# Board1.net
KiCad netlist of a schematic drawn in EasyEDA Pro
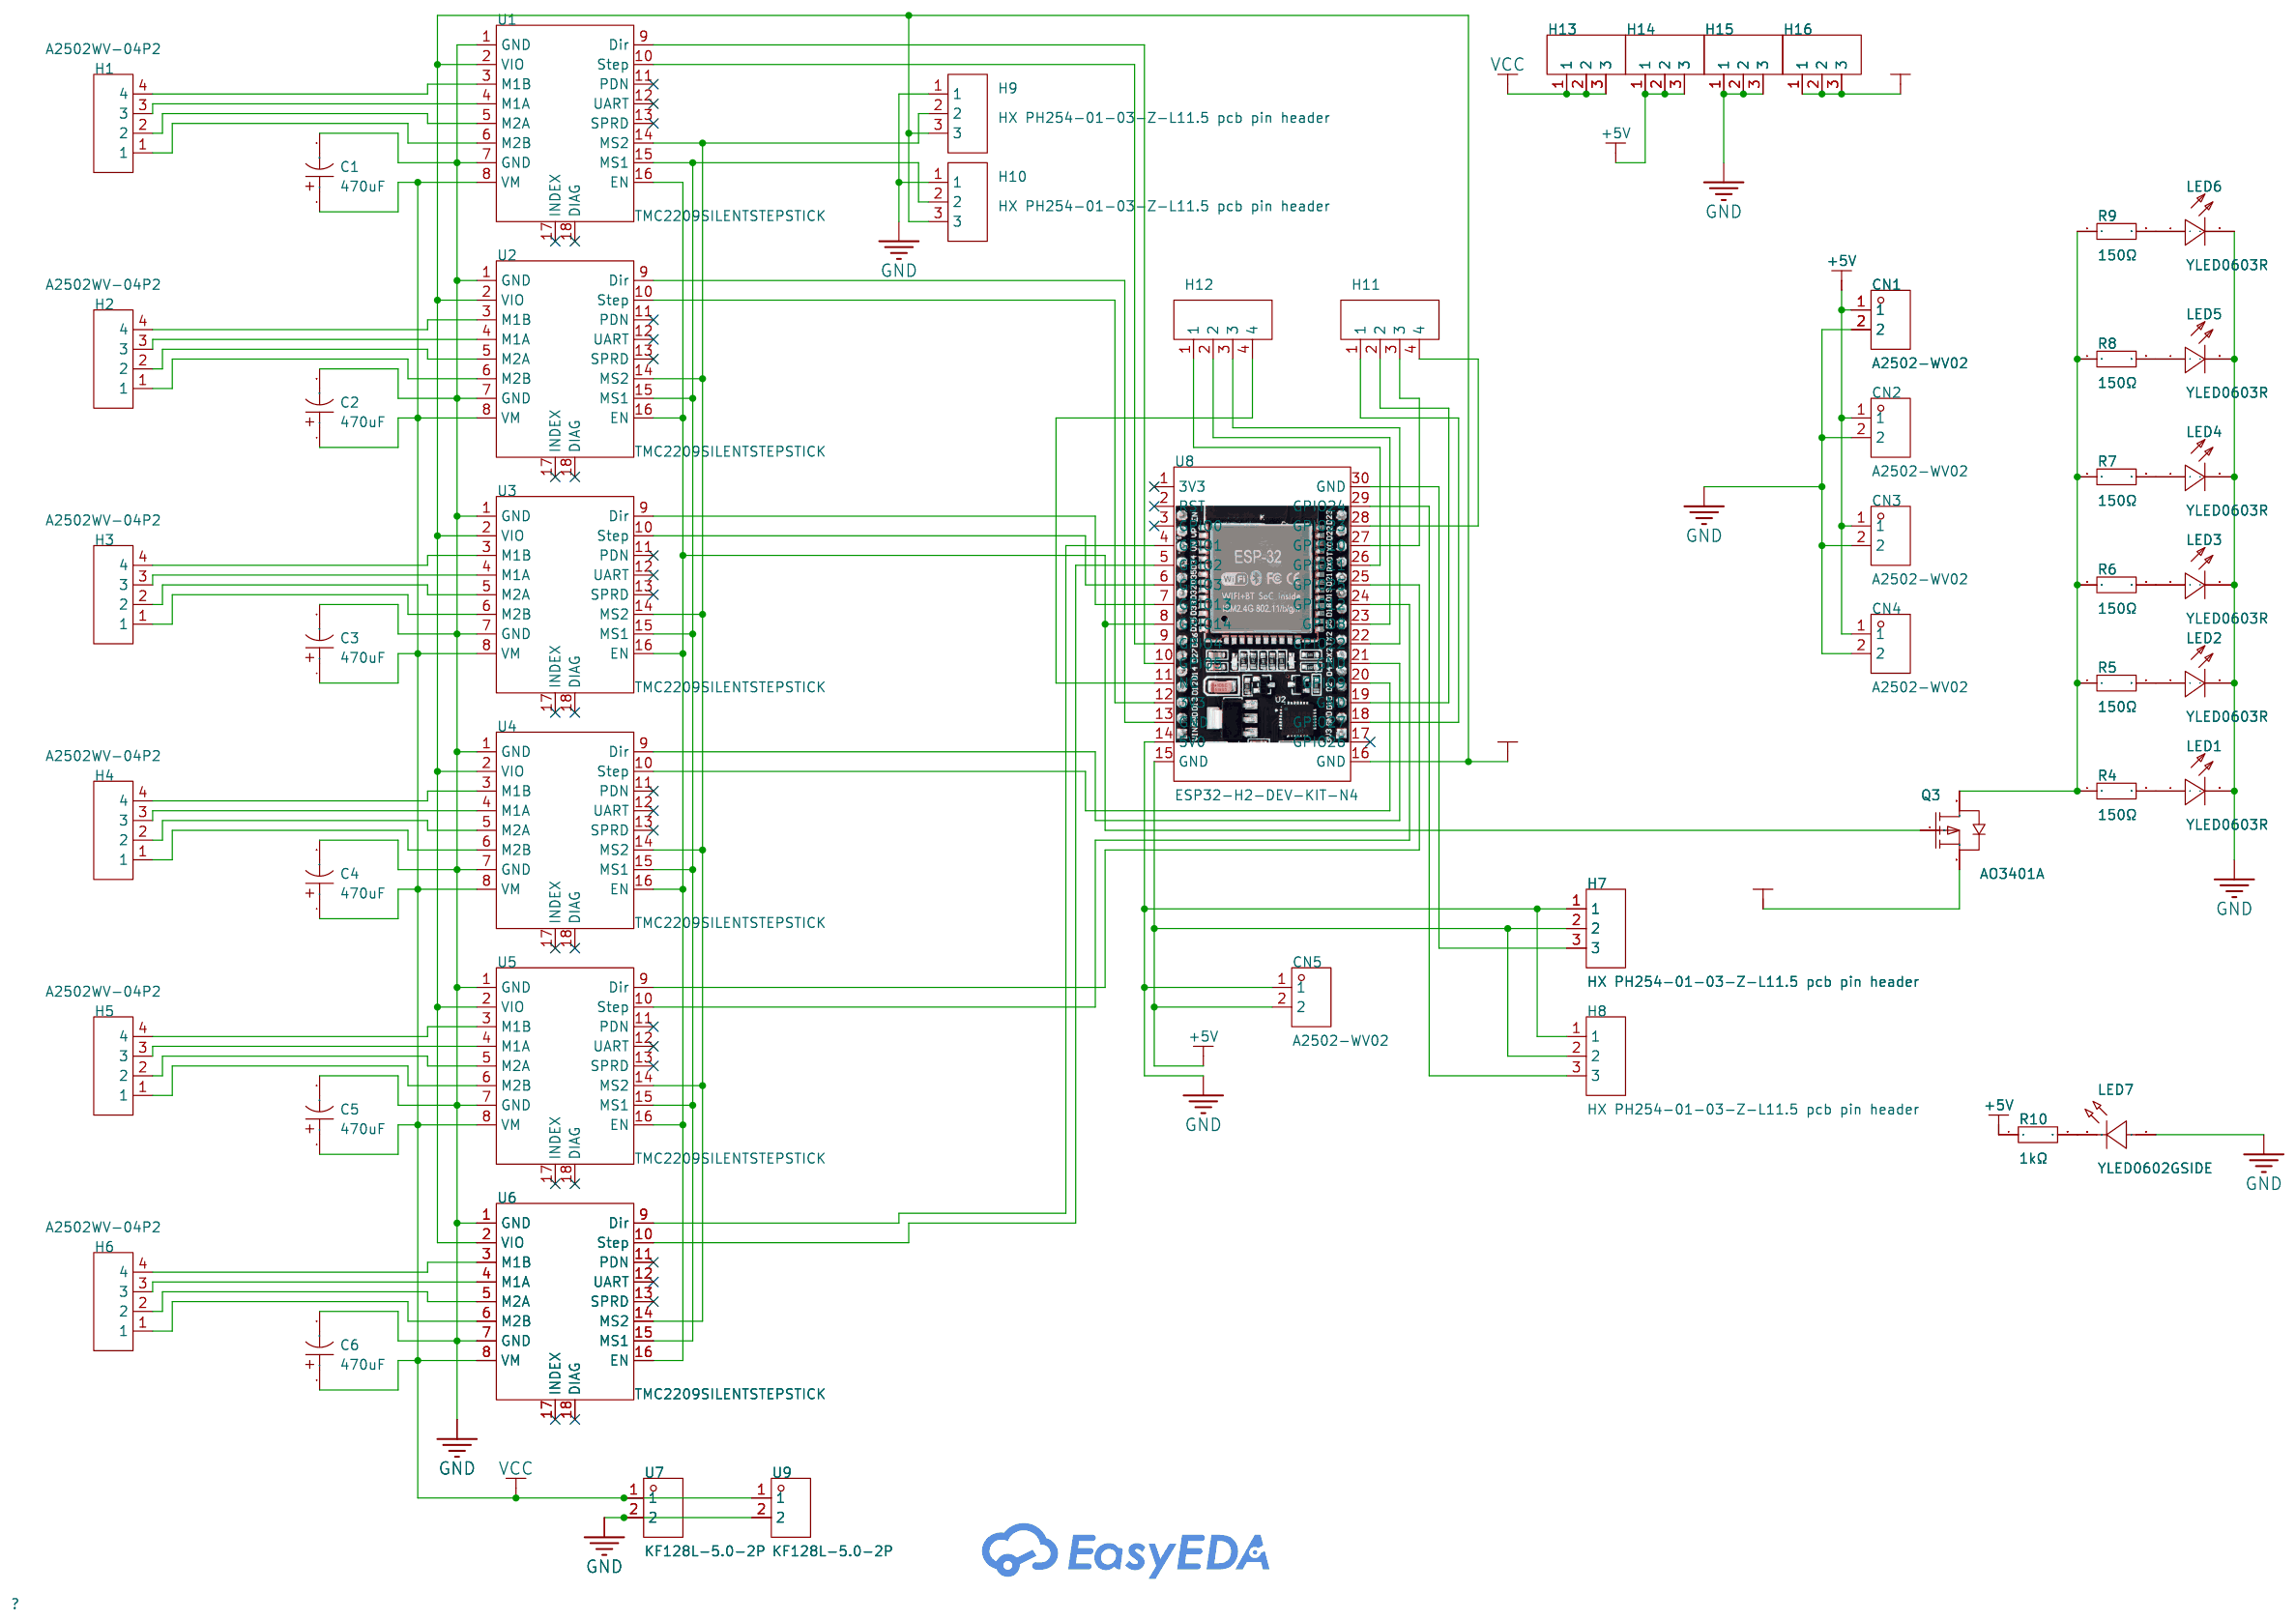
[diagram p0: schematic sheet]

(export (version "E")
  (design (tool "Eeschema 10.0.6"))
  (components
    (comp (ref "C1")
      (value "470uF")
      (footprint "easyedapro:CAP-TH_BD10.0-P5.00-D0.6-FD")
      (fields (field (name "Manufacturer Part") "50V470uF CD288") (field (name "Manufacturer") "HRK(鸿瑞凯电子)"))
      (libsource (lib "easyedapro") (part "50V470UF CD288"))
    )
    (comp (ref "C2")
      (value "470uF")
      (footprint "easyedapro:CAP-TH_BD10.0-P5.00-D0.6-FD")
      (fields (field (name "Manufacturer Part") "50V470uF CD288") (field (name "Manufacturer") "HRK(鸿瑞凯电子)"))
      (libsource (lib "easyedapro") (part "50V470UF CD288"))
    )
    (comp (ref "C3")
      (value "470uF")
      (footprint "easyedapro:CAP-TH_BD10.0-P5.00-D0.6-FD")
      (fields (field (name "Manufacturer Part") "50V470uF CD288") (field (name "Manufacturer") "HRK(鸿瑞凯电子)"))
      (libsource (lib "easyedapro") (part "50V470UF CD288"))
    )
    (comp (ref "C4")
      (value "470uF")
      (footprint "easyedapro:CAP-TH_BD10.0-P5.00-D0.6-FD")
      (fields (field (name "Manufacturer Part") "50V470uF CD288") (field (name "Manufacturer") "HRK(鸿瑞凯电子)"))
      (libsource (lib "easyedapro") (part "50V470UF CD288"))
    )
    (comp (ref "C5")
      (value "470uF")
      (footprint "easyedapro:CAP-TH_BD10.0-P5.00-D0.6-FD")
      (fields (field (name "Manufacturer Part") "50V470uF CD288") (field (name "Manufacturer") "HRK(鸿瑞凯电子)"))
      (libsource (lib "easyedapro") (part "50V470UF CD288"))
    )
    (comp (ref "C6")
      (value "470uF")
      (footprint "easyedapro:CAP-TH_BD10.0-P5.00-D0.6-FD")
      (fields (field (name "Manufacturer Part") "50V470uF CD288") (field (name "Manufacturer") "HRK(鸿瑞凯电子)"))
      (libsource (lib "easyedapro") (part "50V470UF CD288"))
    )
    (comp (ref "CN1")
      (value "A2502-WV02")
      (footprint "easyedapro:CONN-TH_A2502-WV02")
      (libsource (lib "easyedapro") (part "A2502-WV02"))
    )
    (comp (ref "CN2")
      (value "A2502-WV02")
      (footprint "easyedapro:CONN-TH_A2502-WV02")
      (libsource (lib "easyedapro") (part "A2502-WV02"))
    )
    (comp (ref "CN3")
      (value "A2502-WV02")
      (footprint "easyedapro:CONN-TH_A2502-WV02")
      (libsource (lib "easyedapro") (part "A2502-WV02"))
    )
    (comp (ref "CN4")
      (value "A2502-WV02")
      (footprint "easyedapro:CONN-TH_A2502-WV02")
      (libsource (lib "easyedapro") (part "A2502-WV02"))
    )
    (comp (ref "CN5")
      (value "A2502-WV02")
      (footprint "easyedapro:CONN-TH_A2502-WV02")
      (libsource (lib "easyedapro") (part "A2502-WV02"))
    )
    (comp (ref "H1")
      (value "A2502WV-04P2")
      (footprint "easyedapro:HDR-TH_4P-HX-PH254-01-04-Z-L11.5")
      (fields (field (name "Manufacturer") "HR(灿达)"))
      (libsource (lib "easyedapro") (part "HX PH254-01-04-Z-L11.5 STRAIGHT PIN HEADER"))
    )
    (comp (ref "H2")
      (value "A2502WV-04P2")
      (footprint "easyedapro:HDR-TH_4P-HX-PH254-01-04-Z-L11.5")
      (fields (field (name "Manufacturer") "HR(灿达)"))
      (libsource (lib "easyedapro") (part "HX PH254-01-04-Z-L11.5 STRAIGHT PIN HEADER"))
    )
    (comp (ref "H3")
      (value "A2502WV-04P2")
      (footprint "easyedapro:HDR-TH_4P-HX-PH254-01-04-Z-L11.5")
      (fields (field (name "Manufacturer") "HR(灿达)"))
      (libsource (lib "easyedapro") (part "HX PH254-01-04-Z-L11.5 STRAIGHT PIN HEADER"))
    )
    (comp (ref "H4")
      (value "A2502WV-04P2")
      (footprint "easyedapro:HDR-TH_4P-HX-PH254-01-04-Z-L11.5")
      (fields (field (name "Manufacturer") "HR(灿达)"))
      (libsource (lib "easyedapro") (part "HX PH254-01-04-Z-L11.5 STRAIGHT PIN HEADER"))
    )
    (comp (ref "H5")
      (value "A2502WV-04P2")
      (footprint "easyedapro:HDR-TH_4P-HX-PH254-01-04-Z-L11.5")
      (fields (field (name "Manufacturer") "HR(灿达)"))
      (libsource (lib "easyedapro") (part "HX PH254-01-04-Z-L11.5 STRAIGHT PIN HEADER"))
    )
    (comp (ref "H6")
      (value "A2502WV-04P2")
      (footprint "easyedapro:HDR-TH_4P-HX-PH254-01-04-Z-L11.5")
      (fields (field (name "Manufacturer") "HR(灿达)"))
      (libsource (lib "easyedapro") (part "HX PH254-01-04-Z-L11.5 STRAIGHT PIN HEADER"))
    )
    (comp (ref "H7")
      (value "HX PH254-01-03-Z-L11.5 pcb pin header")
      (footprint "easyedapro:HDR-TH_3P-P2.54-V-M-1")
      (fields (field (name "Manufacturer") "hanxia(韩下)"))
      (libsource (lib "easyedapro") (part "HX PH254-01-03-Z-L11.5 PCB PIN HEADER"))
    )
    (comp (ref "H8")
      (value "HX PH254-01-03-Z-L11.5 pcb pin header")
      (footprint "easyedapro:HDR-TH_3P-P2.54-V-M-1")
      (fields (field (name "Manufacturer") "hanxia(韩下)"))
      (libsource (lib "easyedapro") (part "HX PH254-01-03-Z-L11.5 PCB PIN HEADER"))
    )
    (comp (ref "H9")
      (value "HX PH254-01-03-Z-L11.5 pcb pin header")
      (footprint "easyedapro:HDR-TH_3P-P2.54-V-M-1")
      (fields (field (name "Manufacturer") "hanxia(韩下)"))
      (libsource (lib "easyedapro") (part "HX PH254-01-03-Z-L11.5 PCB PIN HEADER"))
    )
    (comp (ref "H10")
      (value "HX PH254-01-03-Z-L11.5 pcb pin header")
      (footprint "easyedapro:HDR-TH_3P-P2.54-V-M-1")
      (fields (field (name "Manufacturer") "hanxia(韩下)"))
      (libsource (lib "easyedapro") (part "HX PH254-01-03-Z-L11.5 PCB PIN HEADER"))
    )
    (comp (ref "H11")
      (value "HX PH254-01-04-Z-L11.5 straight pin header")
      (footprint "easyedapro:HDR-TH_4P-HX-PH254-01-04-Z-L11.5")
      (fields (field (name "Manufacturer") "hanxia(韩下)"))
      (libsource (lib "easyedapro") (part "HX PH254-01-04-Z-L11.5 STRAIGHT PIN HEADER"))
    )
    (comp (ref "H12")
      (value "HX PH254-01-04-Z-L11.5 straight pin header")
      (footprint "easyedapro:HDR-TH_4P-HX-PH254-01-04-Z-L11.5")
      (fields (field (name "Manufacturer") "hanxia(韩下)"))
      (libsource (lib "easyedapro") (part "HX PH254-01-04-Z-L11.5 STRAIGHT PIN HEADER"))
    )
    (comp (ref "H13")
      (value "HX PH254-01-03-Z-L11.5 pcb pin header")
      (footprint "easyedapro:HDR-TH_3P-P2.54-V-M-1")
      (fields (field (name "Manufacturer") "hanxia(韩下)"))
      (libsource (lib "easyedapro") (part "HX PH254-01-03-Z-L11.5 PCB PIN HEADER"))
    )
    (comp (ref "H14")
      (value "HX PH254-01-03-Z-L11.5 pcb pin header")
      (footprint "easyedapro:HDR-TH_3P-P2.54-V-M-1")
      (fields (field (name "Manufacturer") "hanxia(韩下)"))
      (libsource (lib "easyedapro") (part "HX PH254-01-03-Z-L11.5 PCB PIN HEADER"))
    )
    (comp (ref "H15")
      (value "HX PH254-01-03-Z-L11.5 pcb pin header")
      (footprint "easyedapro:HDR-TH_3P-P2.54-V-M-1")
      (fields (field (name "Manufacturer") "hanxia(韩下)"))
      (libsource (lib "easyedapro") (part "HX PH254-01-03-Z-L11.5 PCB PIN HEADER"))
    )
    (comp (ref "H16")
      (value "HX PH254-01-03-Z-L11.5 pcb pin header")
      (footprint "easyedapro:HDR-TH_3P-P2.54-V-M-1")
      (fields (field (name "Manufacturer") "hanxia(韩下)"))
      (libsource (lib "easyedapro") (part "HX PH254-01-03-Z-L11.5 PCB PIN HEADER"))
    )
    (comp (ref "LED1")
      (value "YLED0603R")
      (footprint "easyedapro:LED0603-FD")
      (fields (field (name "Manufacturer") "YONGYUTAI(永裕泰)"))
      (libsource (lib "easyedapro") (part "YLED0603R"))
    )
    (comp (ref "LED2")
      (value "YLED0603R")
      (footprint "easyedapro:LED0603-FD")
      (fields (field (name "Manufacturer") "YONGYUTAI(永裕泰)"))
      (libsource (lib "easyedapro") (part "YLED0603R"))
    )
    (comp (ref "LED3")
      (value "YLED0603R")
      (footprint "easyedapro:LED0603-FD")
      (fields (field (name "Manufacturer") "YONGYUTAI(永裕泰)"))
      (libsource (lib "easyedapro") (part "YLED0603R"))
    )
    (comp (ref "LED4")
      (value "YLED0603R")
      (footprint "easyedapro:LED0603-FD")
      (fields (field (name "Manufacturer") "YONGYUTAI(永裕泰)"))
      (libsource (lib "easyedapro") (part "YLED0603R"))
    )
    (comp (ref "LED5")
      (value "YLED0603R")
      (footprint "easyedapro:LED0603-FD")
      (fields (field (name "Manufacturer") "YONGYUTAI(永裕泰)"))
      (libsource (lib "easyedapro") (part "YLED0603R"))
    )
    (comp (ref "LED6")
      (value "YLED0603R")
      (footprint "easyedapro:LED0603-FD")
      (fields (field (name "Manufacturer") "YONGYUTAI(永裕泰)"))
      (libsource (lib "easyedapro") (part "YLED0603R"))
    )
    (comp (ref "LED7")
      (value "YLED0602GSIDE")
      (footprint "easyedapro:LED-SMD_L1.6-W1.1-R-RD_GREEN")
      (fields (field (name "Manufacturer") "YONGYUTAI(永裕泰)"))
      (libsource (lib "easyedapro") (part "YLED0602GSIDE"))
    )
    (comp (ref "Q3")
      (value "AO3401A")
      (footprint "easyedapro:SOT-23-3_L2.9-W1.3-P1.90-LS2.4-BR")
      (fields (field (name "Manufacturer") "FUXINSEMI(富芯森美)"))
      (libsource (lib "easyedapro") (part "AO3401A_C5380686"))
    )
    (comp (ref "R4")
      (value "150Ω")
      (footprint "easyedapro:R0603")
      (fields (field (name "Manufacturer Part") "RMC06031505%N") (field (name "Manufacturer") "Tyohm(幸亚电阻)"))
      (libsource (lib "easyedapro") (part "0603WAF1001T5E"))
    )
    (comp (ref "R5")
      (value "150Ω")
      (footprint "easyedapro:R0603")
      (fields (field (name "Manufacturer Part") "RMC06031505%N") (field (name "Manufacturer") "Tyohm(幸亚电阻)"))
      (libsource (lib "easyedapro") (part "0603WAF1001T5E"))
    )
    (comp (ref "R6")
      (value "150Ω")
      (footprint "easyedapro:R0603")
      (fields (field (name "Manufacturer Part") "RMC06031505%N") (field (name "Manufacturer") "Tyohm(幸亚电阻)"))
      (libsource (lib "easyedapro") (part "0603WAF1001T5E"))
    )
    (comp (ref "R7")
      (value "150Ω")
      (footprint "easyedapro:R0603")
      (fields (field (name "Manufacturer Part") "RMC06031505%N") (field (name "Manufacturer") "Tyohm(幸亚电阻)"))
      (libsource (lib "easyedapro") (part "0603WAF1001T5E"))
    )
    (comp (ref "R8")
      (value "150Ω")
      (footprint "easyedapro:R0603")
      (fields (field (name "Manufacturer Part") "RMC06031505%N") (field (name "Manufacturer") "Tyohm(幸亚电阻)"))
      (libsource (lib "easyedapro") (part "0603WAF1001T5E"))
    )
    (comp (ref "R9")
      (value "150Ω")
      (footprint "easyedapro:R0603")
      (fields (field (name "Manufacturer Part") "RMC06031505%N") (field (name "Manufacturer") "Tyohm(幸亚电阻)"))
      (libsource (lib "easyedapro") (part "0603WAF1001T5E"))
    )
    (comp (ref "R10")
      (value "1kΩ")
      (footprint "easyedapro:R0603")
      (fields
        (field (name "Manufacturer Part") "0603WAF1001T5E")
        (field (name "Manufacturer") "UNI-ROYAL(厚声)")
      )
      (libsource (lib "easyedapro") (part "0603WAF1001T5E"))
    )
    (comp (ref "U1")
      (value "TMC2209SILENTSTEPSTICK")
      (footprint "easyedapro:COMM-TH_TMC2209SILENTSTEPSTICK")
      (description "Type:Power Management")
      (fields (field (name "Manufacturer") "TRINAMIC"))
      (libsource (lib "easyedapro") (part "TMC2209SILENTSTEPSTICK"))
    )
    (comp (ref "U2")
      (value "TMC2209SILENTSTEPSTICK")
      (footprint "easyedapro:COMM-TH_TMC2209SILENTSTEPSTICK")
      (description "Type:Power Management")
      (fields (field (name "Manufacturer") "TRINAMIC"))
      (libsource (lib "easyedapro") (part "TMC2209SILENTSTEPSTICK"))
    )
    (comp (ref "U3")
      (value "TMC2209SILENTSTEPSTICK")
      (footprint "easyedapro:COMM-TH_TMC2209SILENTSTEPSTICK")
      (description "Type:Power Management")
      (fields (field (name "Manufacturer") "TRINAMIC"))
      (libsource (lib "easyedapro") (part "TMC2209SILENTSTEPSTICK"))
    )
    (comp (ref "U4")
      (value "TMC2209SILENTSTEPSTICK")
      (footprint "easyedapro:COMM-TH_TMC2209SILENTSTEPSTICK")
      (description "Type:Power Management")
      (fields (field (name "Manufacturer") "TRINAMIC"))
      (libsource (lib "easyedapro") (part "TMC2209SILENTSTEPSTICK"))
    )
    (comp (ref "U5")
      (value "TMC2209SILENTSTEPSTICK")
      (footprint "easyedapro:COMM-TH_TMC2209SILENTSTEPSTICK")
      (description "Type:Power Management")
      (fields (field (name "Manufacturer") "TRINAMIC"))
      (libsource (lib "easyedapro") (part "TMC2209SILENTSTEPSTICK"))
    )
    (comp (ref "U6")
      (value "TMC2209SILENTSTEPSTICK")
      (footprint "easyedapro:COMM-TH_TMC2209SILENTSTEPSTICK")
      (description "Type:Power Management")
      (fields (field (name "Manufacturer") "TRINAMIC"))
      (libsource (lib "easyedapro") (part "TMC2209SILENTSTEPSTICK"))
    )
    (comp (ref "U7")
      (value "KF128L-5.0-2P")
      (footprint "easyedapro:CONN-TH_P5.00_KF128L-5.0-2P")
      (fields (field (name "Manufacturer") "KEFA(科发)"))
      (libsource (lib "easyedapro") (part "KF128L-5.0-2P"))
    )
    (comp (ref "U8")
      (value "ESP32-H2-DEV-KIT-N4")
      (footprint "easyedapro:COMM-TH_L51.6-W25.4-P2.54-LS22.86")
      (libsource (lib "easyedapro") (part "ESP32-H2-DEV-KIT-N4"))
    )
    (comp (ref "U9")
      (value "KF128L-5.0-2P")
      (footprint "easyedapro:CONN-TH_P5.00_KF128L-5.0-2P")
      (fields (field (name "Manufacturer") "KEFA(科发)"))
      (libsource (lib "easyedapro") (part "KF128L-5.0-2P"))
    )
  )
  (nets
    (net (code "1") (name "+3V3") (class "Default")
      (node (ref "H10") (pin "3") (pinfunction "3_3") (pintype "unspecified"))
      (node (ref "H16") (pin "1") (pinfunction "1_1") (pintype "unspecified"))
      (node (ref "H16") (pin "2") (pinfunction "2_2") (pintype "unspecified"))
      (node (ref "H16") (pin "3") (pinfunction "3_3") (pintype "unspecified"))
      (node (ref "H9") (pin "3") (pinfunction "3_3") (pintype "unspecified"))
      (node (ref "Q3") (pin "2") (pinfunction "S_2") (pintype "unspecified"))
      (node (ref "U1") (pin "2") (pinfunction "VIO_2") (pintype "unspecified"))
      (node (ref "U2") (pin "2") (pinfunction "VIO_2") (pintype "unspecified"))
      (node (ref "U3") (pin "2") (pinfunction "VIO_2") (pintype "unspecified"))
      (node (ref "U4") (pin "2") (pinfunction "VIO_2") (pintype "unspecified"))
      (node (ref "U5") (pin "2") (pinfunction "VIO_2") (pintype "unspecified"))
      (node (ref "U6") (pin "2") (pinfunction "VIO_2") (pintype "unspecified"))
      (node (ref "U8") (pin "16") (pinfunction "GND_16") (pintype "unspecified"))
    )
    (net (code "2") (name "+5V") (class "Default")
      (node (ref "CN1") (pin "1") (pinfunction "1_1") (pintype "unspecified"))
      (node (ref "CN2") (pin "1") (pinfunction "1_1") (pintype "unspecified"))
      (node (ref "CN3") (pin "1") (pinfunction "1_1") (pintype "unspecified"))
      (node (ref "CN4") (pin "1") (pinfunction "1_1") (pintype "unspecified"))
      (node (ref "CN5") (pin "2") (pinfunction "2_2") (pintype "unspecified"))
      (node (ref "H14") (pin "1") (pinfunction "1_1") (pintype "unspecified"))
      (node (ref "H14") (pin "2") (pinfunction "2_2") (pintype "unspecified"))
      (node (ref "H14") (pin "3") (pinfunction "3_3") (pintype "unspecified"))
      (node (ref "H7") (pin "2") (pinfunction "2_2") (pintype "unspecified"))
      (node (ref "H8") (pin "2") (pinfunction "2_2") (pintype "unspecified"))
      (node (ref "R10") (pin "1") (pinfunction "1_1") (pintype "input"))
      (node (ref "U8") (pin "15") (pinfunction "GND_15") (pintype "unspecified"))
    )
    (net (code "3") (name "GND") (class "Default")
      (node (ref "C1") (pin "2") (pinfunction "2_2") (pintype "input"))
      (node (ref "C2") (pin "2") (pinfunction "2_2") (pintype "input"))
      (node (ref "C3") (pin "2") (pinfunction "2_2") (pintype "input"))
      (node (ref "C4") (pin "2") (pinfunction "2_2") (pintype "input"))
      (node (ref "C5") (pin "2") (pinfunction "2_2") (pintype "input"))
      (node (ref "C6") (pin "2") (pinfunction "2_2") (pintype "input"))
      (node (ref "CN1") (pin "2") (pinfunction "2_2") (pintype "unspecified"))
      (node (ref "CN2") (pin "2") (pinfunction "2_2") (pintype "unspecified"))
      (node (ref "CN3") (pin "2") (pinfunction "2_2") (pintype "unspecified"))
      (node (ref "CN4") (pin "2") (pinfunction "2_2") (pintype "unspecified"))
      (node (ref "CN5") (pin "1") (pinfunction "1_1") (pintype "unspecified"))
      (node (ref "H10") (pin "1") (pinfunction "1_1") (pintype "unspecified"))
      (node (ref "H15") (pin "1") (pinfunction "1_1") (pintype "unspecified"))
      (node (ref "H15") (pin "2") (pinfunction "2_2") (pintype "unspecified"))
      (node (ref "H15") (pin "3") (pinfunction "3_3") (pintype "unspecified"))
      (node (ref "H7") (pin "1") (pinfunction "1_1") (pintype "unspecified"))
      (node (ref "H8") (pin "1") (pinfunction "1_1") (pintype "unspecified"))
      (node (ref "H9") (pin "1") (pinfunction "1_1") (pintype "unspecified"))
      (node (ref "LED1") (pin "2") (pinfunction "-_2") (pintype "unspecified"))
      (node (ref "LED2") (pin "2") (pinfunction "-_2") (pintype "unspecified"))
      (node (ref "LED3") (pin "2") (pinfunction "-_2") (pintype "unspecified"))
      (node (ref "LED4") (pin "2") (pinfunction "-_2") (pintype "unspecified"))
      (node (ref "LED5") (pin "2") (pinfunction "-_2") (pintype "unspecified"))
      (node (ref "LED6") (pin "2") (pinfunction "-_2") (pintype "unspecified"))
      (node (ref "LED7") (pin "1") (pinfunction "A_1") (pintype "unspecified"))
      (node (ref "U1") (pin "1") (pinfunction "GND_1") (pintype "unspecified"))
      (node (ref "U1") (pin "7") (pinfunction "GND_7") (pintype "unspecified"))
      (node (ref "U2") (pin "1") (pinfunction "GND_1") (pintype "unspecified"))
      (node (ref "U2") (pin "7") (pinfunction "GND_7") (pintype "unspecified"))
      (node (ref "U3") (pin "1") (pinfunction "GND_1") (pintype "unspecified"))
      (node (ref "U3") (pin "7") (pinfunction "GND_7") (pintype "unspecified"))
      (node (ref "U4") (pin "1") (pinfunction "GND_1") (pintype "unspecified"))
      (node (ref "U4") (pin "7") (pinfunction "GND_7") (pintype "unspecified"))
      (node (ref "U5") (pin "1") (pinfunction "GND_1") (pintype "unspecified"))
      (node (ref "U5") (pin "7") (pinfunction "GND_7") (pintype "unspecified"))
      (node (ref "U6") (pin "1") (pinfunction "GND_1") (pintype "unspecified"))
      (node (ref "U6") (pin "7") (pinfunction "GND_7") (pintype "unspecified"))
      (node (ref "U7") (pin "2") (pinfunction "2_2") (pintype "unspecified"))
      (node (ref "U8") (pin "14") (pinfunction "5V0_14") (pintype "unspecified"))
      (node (ref "U9") (pin "2") (pinfunction "2_2") (pintype "unspecified"))
    )
    (net (code "4") (name "Net-(H7-Pad3)") (class "Default")
      (node (ref "H7") (pin "3") (pinfunction "3_3") (pintype "unspecified"))
      (node (ref "U8") (pin "30") (pinfunction "GND_30") (pintype "unspecified"))
    )
    (net (code "5") (name "Net-(H11-Pad2)") (class "Default")
      (node (ref "H11") (pin "2") (pinfunction "2_2") (pintype "unspecified"))
      (node (ref "U8") (pin "19") (pinfunction "GND_19") (pintype "unspecified"))
    )
    (net (code "6") (name "Net-(LED1-+)") (class "Default")
      (node (ref "LED1") (pin "1") (pinfunction "+_1") (pintype "unspecified"))
      (node (ref "R4") (pin "2") (pinfunction "2_2") (pintype "input"))
    )
    (net (code "7") (name "Net-(LED2-+)") (class "Default")
      (node (ref "LED2") (pin "1") (pinfunction "+_1") (pintype "unspecified"))
      (node (ref "R5") (pin "2") (pinfunction "2_2") (pintype "input"))
    )
    (net (code "8") (name "Net-(LED3-+)") (class "Default")
      (node (ref "LED3") (pin "1") (pinfunction "+_1") (pintype "unspecified"))
      (node (ref "R6") (pin "2") (pinfunction "2_2") (pintype "input"))
    )
    (net (code "9") (name "Net-(LED4-+)") (class "Default")
      (node (ref "LED4") (pin "1") (pinfunction "+_1") (pintype "unspecified"))
      (node (ref "R7") (pin "2") (pinfunction "2_2") (pintype "input"))
    )
    (net (code "10") (name "Net-(LED5-+)") (class "Default")
      (node (ref "LED5") (pin "1") (pinfunction "+_1") (pintype "unspecified"))
      (node (ref "R8") (pin "2") (pinfunction "2_2") (pintype "input"))
    )
    (net (code "11") (name "Net-(LED6-+)") (class "Default")
      (node (ref "LED6") (pin "1") (pinfunction "+_1") (pintype "unspecified"))
      (node (ref "R9") (pin "2") (pinfunction "2_2") (pintype "input"))
    )
    (net (code "12") (name "Net-(LED7-K)") (class "Default")
      (node (ref "LED7") (pin "2") (pinfunction "K_2") (pintype "unspecified"))
      (node (ref "R10") (pin "2") (pinfunction "2_2") (pintype "input"))
    )
    (net (code "13") (name "Net-(Q3-D)") (class "Default")
      (node (ref "Q3") (pin "3") (pinfunction "D_3") (pintype "unspecified"))
      (node (ref "R4") (pin "1") (pinfunction "1_1") (pintype "input"))
      (node (ref "R5") (pin "1") (pinfunction "1_1") (pintype "input"))
      (node (ref "R6") (pin "1") (pinfunction "1_1") (pintype "input"))
      (node (ref "R7") (pin "1") (pinfunction "1_1") (pintype "input"))
      (node (ref "R8") (pin "1") (pinfunction "1_1") (pintype "input"))
      (node (ref "R9") (pin "1") (pinfunction "1_1") (pintype "input"))
    )
    (net (code "14") (name "Net-(Q3-G)") (class "Default")
      (node (ref "Q3") (pin "1") (pinfunction "G_1") (pintype "unspecified"))
      (node (ref "U1") (pin "16") (pinfunction "EN_16") (pintype "unspecified"))
      (node (ref "U2") (pin "16") (pinfunction "EN_16") (pintype "unspecified"))
      (node (ref "U3") (pin "16") (pinfunction "EN_16") (pintype "unspecified"))
      (node (ref "U4") (pin "16") (pinfunction "EN_16") (pintype "unspecified"))
      (node (ref "U5") (pin "16") (pinfunction "EN_16") (pintype "unspecified"))
      (node (ref "U6") (pin "16") (pinfunction "EN_16") (pintype "unspecified"))
      (node (ref "U8") (pin "8") (pinfunction "GPIO14_8") (pintype "unspecified"))
    )
    (net (code "15") (name "Net-(U1-Dir)") (class "Default")
      (node (ref "U1") (pin "9") (pinfunction "Dir_9") (pintype "unspecified"))
      (node (ref "U8") (pin "10") (pinfunction "GPIO5_10") (pintype "unspecified"))
    )
    (net (code "16") (name "Net-(U1-M1A)") (class "Default")
      (node (ref "H1") (pin "3") (pinfunction "3_3") (pintype "unspecified"))
      (node (ref "U1") (pin "4") (pinfunction "M1A_4") (pintype "unspecified"))
    )
    (net (code "17") (name "Net-(U1-M1B)") (class "Default")
      (node (ref "H1") (pin "4") (pinfunction "4_4") (pintype "unspecified"))
      (node (ref "U1") (pin "3") (pinfunction "M1B_3") (pintype "unspecified"))
    )
    (net (code "18") (name "Net-(U1-M2A)") (class "Default")
      (node (ref "H1") (pin "2") (pinfunction "2_2") (pintype "unspecified"))
      (node (ref "U1") (pin "5") (pinfunction "M2A_5") (pintype "unspecified"))
    )
    (net (code "19") (name "Net-(U1-M2B)") (class "Default")
      (node (ref "H1") (pin "1") (pinfunction "1_1") (pintype "unspecified"))
      (node (ref "U1") (pin "6") (pinfunction "M2B_6") (pintype "unspecified"))
    )
    (net (code "20") (name "Net-(U1-MS1)") (class "Default")
      (node (ref "H10") (pin "2") (pinfunction "2_2") (pintype "unspecified"))
      (node (ref "U1") (pin "15") (pinfunction "MS1_15") (pintype "unspecified"))
      (node (ref "U2") (pin "15") (pinfunction "MS1_15") (pintype "unspecified"))
      (node (ref "U3") (pin "15") (pinfunction "MS1_15") (pintype "unspecified"))
      (node (ref "U4") (pin "15") (pinfunction "MS1_15") (pintype "unspecified"))
      (node (ref "U5") (pin "15") (pinfunction "MS1_15") (pintype "unspecified"))
      (node (ref "U6") (pin "15") (pinfunction "MS1_15") (pintype "unspecified"))
    )
    (net (code "21") (name "Net-(U1-MS2)") (class "Default")
      (node (ref "H9") (pin "2") (pinfunction "2_2") (pintype "unspecified"))
      (node (ref "U1") (pin "14") (pinfunction "MS2_14") (pintype "unspecified"))
      (node (ref "U2") (pin "14") (pinfunction "MS2_14") (pintype "unspecified"))
      (node (ref "U3") (pin "14") (pinfunction "MS2_14") (pintype "unspecified"))
      (node (ref "U4") (pin "14") (pinfunction "MS2_14") (pintype "unspecified"))
      (node (ref "U5") (pin "14") (pinfunction "MS2_14") (pintype "unspecified"))
      (node (ref "U6") (pin "14") (pinfunction "MS2_14") (pintype "unspecified"))
    )
    (net (code "22") (name "Net-(U1-Step)") (class "Default")
      (node (ref "U1") (pin "10") (pinfunction "Step_10") (pintype "unspecified"))
      (node (ref "U8") (pin "9") (pinfunction "GPIO4_9") (pintype "unspecified"))
    )
    (net (code "23") (name "Net-(U2-Dir)") (class "Default")
      (node (ref "U2") (pin "9") (pinfunction "Dir_9") (pintype "unspecified"))
      (node (ref "U8") (pin "13") (pinfunction "GND_13") (pintype "unspecified"))
    )
    (net (code "24") (name "Net-(U2-M1A)") (class "Default")
      (node (ref "H2") (pin "3") (pinfunction "3_3") (pintype "unspecified"))
      (node (ref "U2") (pin "4") (pinfunction "M1A_4") (pintype "unspecified"))
    )
    (net (code "25") (name "Net-(U2-M1B)") (class "Default")
      (node (ref "H2") (pin "4") (pinfunction "4_4") (pintype "unspecified"))
      (node (ref "U2") (pin "3") (pinfunction "M1B_3") (pintype "unspecified"))
    )
    (net (code "26") (name "Net-(U2-M2A)") (class "Default")
      (node (ref "H2") (pin "2") (pinfunction "2_2") (pintype "unspecified"))
      (node (ref "U2") (pin "5") (pinfunction "M2A_5") (pintype "unspecified"))
    )
    (net (code "27") (name "Net-(U2-M2B)") (class "Default")
      (node (ref "H2") (pin "1") (pinfunction "1_1") (pintype "unspecified"))
      (node (ref "U2") (pin "6") (pinfunction "M2B_6") (pintype "unspecified"))
    )
    (net (code "28") (name "Net-(U2-Step)") (class "Default")
      (node (ref "U2") (pin "10") (pinfunction "Step_10") (pintype "unspecified"))
      (node (ref "U8") (pin "12") (pinfunction "3V3_12") (pintype "unspecified"))
    )
    (net (code "29") (name "Net-(U3-Dir)") (class "Default")
      (node (ref "U3") (pin "9") (pinfunction "Dir_9") (pintype "unspecified"))
      (node (ref "U8") (pin "7") (pinfunction "GPIO13_7") (pintype "unspecified"))
    )
    (net (code "30") (name "Net-(U3-M1A)") (class "Default")
      (node (ref "H3") (pin "3") (pinfunction "3_3") (pintype "unspecified"))
      (node (ref "U3") (pin "4") (pinfunction "M1A_4") (pintype "unspecified"))
    )
    (net (code "31") (name "Net-(U3-M1B)") (class "Default")
      (node (ref "H3") (pin "4") (pinfunction "4_4") (pintype "unspecified"))
      (node (ref "U3") (pin "3") (pinfunction "M1B_3") (pintype "unspecified"))
    )
    (net (code "32") (name "Net-(U3-M2A)") (class "Default")
      (node (ref "H3") (pin "2") (pinfunction "2_2") (pintype "unspecified"))
      (node (ref "U3") (pin "5") (pinfunction "M2A_5") (pintype "unspecified"))
    )
    (net (code "33") (name "Net-(U3-M2B)") (class "Default")
      (node (ref "H3") (pin "1") (pinfunction "1_1") (pintype "unspecified"))
      (node (ref "U3") (pin "6") (pinfunction "M2B_6") (pintype "unspecified"))
    )
    (net (code "34") (name "Net-(U3-Step)") (class "Default")
      (node (ref "U3") (pin "10") (pinfunction "Step_10") (pintype "unspecified"))
      (node (ref "U8") (pin "6") (pinfunction "GPIO3_6") (pintype "unspecified"))
    )
    (net (code "35") (name "Net-(U4-Dir)") (class "Default")
      (node (ref "U4") (pin "9") (pinfunction "Dir_9") (pintype "unspecified"))
      (node (ref "U8") (pin "21") (pinfunction "GND_21") (pintype "unspecified"))
    )
    (net (code "36") (name "Net-(U4-M1A)") (class "Default")
      (node (ref "H4") (pin "3") (pinfunction "3_3") (pintype "unspecified"))
      (node (ref "U4") (pin "4") (pinfunction "M1A_4") (pintype "unspecified"))
    )
    (net (code "37") (name "Net-(U4-M1B)") (class "Default")
      (node (ref "H4") (pin "4") (pinfunction "4_4") (pintype "unspecified"))
      (node (ref "U4") (pin "3") (pinfunction "M1B_3") (pintype "unspecified"))
    )
    (net (code "38") (name "Net-(U4-M2A)") (class "Default")
      (node (ref "H4") (pin "2") (pinfunction "2_2") (pintype "unspecified"))
      (node (ref "U4") (pin "5") (pinfunction "M2A_5") (pintype "unspecified"))
    )
    (net (code "39") (name "Net-(U4-M2B)") (class "Default")
      (node (ref "H4") (pin "1") (pinfunction "1_1") (pintype "unspecified"))
      (node (ref "U4") (pin "6") (pinfunction "M2B_6") (pintype "unspecified"))
    )
    (net (code "40") (name "Net-(U4-Step)") (class "Default")
      (node (ref "U4") (pin "10") (pinfunction "Step_10") (pintype "unspecified"))
      (node (ref "U8") (pin "20") (pinfunction "GPIO9_20") (pintype "unspecified"))
    )
    (net (code "41") (name "Net-(U5-Dir)") (class "Default")
      (node (ref "U5") (pin "9") (pinfunction "Dir_9") (pintype "unspecified"))
      (node (ref "U8") (pin "25") (pinfunction "GPIO25_25") (pintype "unspecified"))
    )
    (net (code "42") (name "Net-(U5-M1A)") (class "Default")
      (node (ref "H5") (pin "3") (pinfunction "3_3") (pintype "unspecified"))
      (node (ref "U5") (pin "4") (pinfunction "M1A_4") (pintype "unspecified"))
    )
    (net (code "43") (name "Net-(U5-M1B)") (class "Default")
      (node (ref "H5") (pin "4") (pinfunction "4_4") (pintype "unspecified"))
      (node (ref "U5") (pin "3") (pinfunction "M1B_3") (pintype "unspecified"))
    )
    (net (code "44") (name "Net-(U5-M2A)") (class "Default")
      (node (ref "H5") (pin "2") (pinfunction "2_2") (pintype "unspecified"))
      (node (ref "U5") (pin "5") (pinfunction "M2A_5") (pintype "unspecified"))
    )
    (net (code "45") (name "Net-(U5-M2B)") (class "Default")
      (node (ref "H5") (pin "1") (pinfunction "1_1") (pintype "unspecified"))
      (node (ref "U5") (pin "6") (pinfunction "M2B_6") (pintype "unspecified"))
    )
    (net (code "46") (name "Net-(U5-Step)") (class "Default")
      (node (ref "U5") (pin "10") (pinfunction "Step_10") (pintype "unspecified"))
      (node (ref "U8") (pin "24") (pinfunction "GPIO12_24") (pintype "unspecified"))
    )
    (net (code "47") (name "Net-(U6-Dir)") (class "Default")
      (node (ref "U6") (pin "9") (pinfunction "Dir_9") (pintype "unspecified"))
      (node (ref "U8") (pin "4") (pinfunction "GPIO1_4") (pintype "unspecified"))
    )
    (net (code "48") (name "Net-(U6-M1A)") (class "Default")
      (node (ref "H6") (pin "3") (pinfunction "3_3") (pintype "unspecified"))
      (node (ref "U6") (pin "4") (pinfunction "M1A_4") (pintype "unspecified"))
    )
    (net (code "49") (name "Net-(U6-M1B)") (class "Default")
      (node (ref "H6") (pin "4") (pinfunction "4_4") (pintype "unspecified"))
      (node (ref "U6") (pin "3") (pinfunction "M1B_3") (pintype "unspecified"))
    )
    (net (code "50") (name "Net-(U6-M2A)") (class "Default")
      (node (ref "H6") (pin "2") (pinfunction "2_2") (pintype "unspecified"))
      (node (ref "U6") (pin "5") (pinfunction "M2A_5") (pintype "unspecified"))
    )
    (net (code "51") (name "Net-(U6-M2B)") (class "Default")
      (node (ref "H6") (pin "1") (pinfunction "1_1") (pintype "unspecified"))
      (node (ref "U6") (pin "6") (pinfunction "M2B_6") (pintype "unspecified"))
    )
    (net (code "52") (name "Net-(U6-Step)") (class "Default")
      (node (ref "U6") (pin "10") (pinfunction "Step_10") (pintype "unspecified"))
      (node (ref "U8") (pin "5") (pinfunction "GPIO2_5") (pintype "unspecified"))
    )
    (net (code "53") (name "Net-(U8-GPIO8)") (class "Default")
      (node (ref "H12") (pin "2") (pinfunction "2_2") (pintype "unspecified"))
      (node (ref "U8") (pin "23") (pinfunction "GPIO8_23") (pintype "unspecified"))
    )
    (net (code "54") (name "Net-(U8-GPIO10)") (class "Default")
      (node (ref "H11") (pin "3") (pinfunction "3_3") (pintype "unspecified"))
      (node (ref "U8") (pin "27") (pinfunction "GPIO10_27") (pintype "unspecified"))
    )
    (net (code "55") (name "Net-(U8-GPIO11)") (class "Default")
      (node (ref "H12") (pin "1") (pinfunction "1_1") (pintype "unspecified"))
      (node (ref "U8") (pin "26") (pinfunction "GPIO11_26") (pintype "unspecified"))
    )
    (net (code "56") (name "Net-(U8-GPIO22)") (class "Default")
      (node (ref "H12") (pin "3") (pinfunction "3_3") (pintype "unspecified"))
      (node (ref "U8") (pin "22") (pinfunction "GPIO22_22") (pintype "unspecified"))
    )
    (net (code "57") (name "Net-(U8-GPIO23)") (class "Default")
      (node (ref "H11") (pin "4") (pinfunction "4_4") (pintype "unspecified"))
      (node (ref "U8") (pin "28") (pinfunction "GPIO23_28") (pintype "unspecified"))
    )
    (net (code "58") (name "Net-(U8-GPIO24)") (class "Default")
      (node (ref "H8") (pin "3") (pinfunction "3_3") (pintype "unspecified"))
      (node (ref "U8") (pin "29") (pinfunction "GPIO24_29") (pintype "unspecified"))
    )
    (net (code "59") (name "Net-(U8-GPIO27)") (class "Default")
      (node (ref "H11") (pin "1") (pinfunction "1_1") (pintype "unspecified"))
      (node (ref "U8") (pin "18") (pinfunction "GPIO27_18") (pintype "unspecified"))
    )
    (net (code "60") (name "Net-(U8-NC)") (class "Default")
      (node (ref "H12") (pin "4") (pinfunction "4_4") (pintype "unspecified"))
      (node (ref "U8") (pin "11") (pinfunction "NC_11") (pintype "unspecified"))
    )
    (net (code "61") (name "VCC") (class "Default")
      (node (ref "C1") (pin "1") (pinfunction "1_1") (pintype "input"))
      (node (ref "C2") (pin "1") (pinfunction "1_1") (pintype "input"))
      (node (ref "C3") (pin "1") (pinfunction "1_1") (pintype "input"))
      (node (ref "C4") (pin "1") (pinfunction "1_1") (pintype "input"))
      (node (ref "C5") (pin "1") (pinfunction "1_1") (pintype "input"))
      (node (ref "C6") (pin "1") (pinfunction "1_1") (pintype "input"))
      (node (ref "H13") (pin "1") (pinfunction "1_1") (pintype "unspecified"))
      (node (ref "H13") (pin "2") (pinfunction "2_2") (pintype "unspecified"))
      (node (ref "H13") (pin "3") (pinfunction "3_3") (pintype "unspecified"))
      (node (ref "U1") (pin "8") (pinfunction "VM_8") (pintype "unspecified"))
      (node (ref "U2") (pin "8") (pinfunction "VM_8") (pintype "unspecified"))
      (node (ref "U3") (pin "8") (pinfunction "VM_8") (pintype "unspecified"))
      (node (ref "U4") (pin "8") (pinfunction "VM_8") (pintype "unspecified"))
      (node (ref "U5") (pin "8") (pinfunction "VM_8") (pintype "unspecified"))
      (node (ref "U6") (pin "8") (pinfunction "VM_8") (pintype "unspecified"))
      (node (ref "U7") (pin "1") (pinfunction "1_1") (pintype "unspecified"))
      (node (ref "U9") (pin "1") (pinfunction "1_1") (pintype "unspecified"))
    )
    (net (code "62") (name "unconnected-(U1-DIAG-Pad18)") (class "Default")
      (node (ref "U1") (pin "18") (pinfunction "DIAG_18") (pintype "unspecified+no_connect"))
    )
    (net (code "63") (name "unconnected-(U1-INDEX-Pad17)") (class "Default")
      (node (ref "U1") (pin "17") (pinfunction "INDEX_17") (pintype "unspecified+no_connect"))
    )
    (net (code "64") (name "unconnected-(U1-PDN-Pad11)") (class "Default")
      (node (ref "U1") (pin "11") (pinfunction "PDN_11") (pintype "unspecified+no_connect"))
    )
    (net (code "65") (name "unconnected-(U1-SPRD-Pad13)") (class "Default")
      (node (ref "U1") (pin "13") (pinfunction "SPRD_13") (pintype "unspecified+no_connect"))
    )
    (net (code "66") (name "unconnected-(U1-UART-Pad12)") (class "Default")
      (node (ref "U1") (pin "12") (pinfunction "UART_12") (pintype "unspecified+no_connect"))
    )
    (net (code "67") (name "unconnected-(U2-DIAG-Pad18)") (class "Default")
      (node (ref "U2") (pin "18") (pinfunction "DIAG_18") (pintype "unspecified+no_connect"))
    )
    (net (code "68") (name "unconnected-(U2-INDEX-Pad17)") (class "Default")
      (node (ref "U2") (pin "17") (pinfunction "INDEX_17") (pintype "unspecified+no_connect"))
    )
    (net (code "69") (name "unconnected-(U2-PDN-Pad11)") (class "Default")
      (node (ref "U2") (pin "11") (pinfunction "PDN_11") (pintype "unspecified+no_connect"))
    )
    (net (code "70") (name "unconnected-(U2-SPRD-Pad13)") (class "Default")
      (node (ref "U2") (pin "13") (pinfunction "SPRD_13") (pintype "unspecified+no_connect"))
    )
    (net (code "71") (name "unconnected-(U2-UART-Pad12)") (class "Default")
      (node (ref "U2") (pin "12") (pinfunction "UART_12") (pintype "unspecified+no_connect"))
    )
    (net (code "72") (name "unconnected-(U3-DIAG-Pad18)") (class "Default")
      (node (ref "U3") (pin "18") (pinfunction "DIAG_18") (pintype "unspecified+no_connect"))
    )
    (net (code "73") (name "unconnected-(U3-INDEX-Pad17)") (class "Default")
      (node (ref "U3") (pin "17") (pinfunction "INDEX_17") (pintype "unspecified+no_connect"))
    )
    (net (code "74") (name "unconnected-(U3-PDN-Pad11)") (class "Default")
      (node (ref "U3") (pin "11") (pinfunction "PDN_11") (pintype "unspecified+no_connect"))
    )
    (net (code "75") (name "unconnected-(U3-SPRD-Pad13)") (class "Default")
      (node (ref "U3") (pin "13") (pinfunction "SPRD_13") (pintype "unspecified+no_connect"))
    )
    (net (code "76") (name "unconnected-(U3-UART-Pad12)") (class "Default")
      (node (ref "U3") (pin "12") (pinfunction "UART_12") (pintype "unspecified+no_connect"))
    )
    (net (code "77") (name "unconnected-(U4-DIAG-Pad18)") (class "Default")
      (node (ref "U4") (pin "18") (pinfunction "DIAG_18") (pintype "unspecified+no_connect"))
    )
    (net (code "78") (name "unconnected-(U4-INDEX-Pad17)") (class "Default")
      (node (ref "U4") (pin "17") (pinfunction "INDEX_17") (pintype "unspecified+no_connect"))
    )
    (net (code "79") (name "unconnected-(U4-PDN-Pad11)") (class "Default")
      (node (ref "U4") (pin "11") (pinfunction "PDN_11") (pintype "unspecified+no_connect"))
    )
    (net (code "80") (name "unconnected-(U4-SPRD-Pad13)") (class "Default")
      (node (ref "U4") (pin "13") (pinfunction "SPRD_13") (pintype "unspecified+no_connect"))
    )
    (net (code "81") (name "unconnected-(U4-UART-Pad12)") (class "Default")
      (node (ref "U4") (pin "12") (pinfunction "UART_12") (pintype "unspecified+no_connect"))
    )
    (net (code "82") (name "unconnected-(U5-DIAG-Pad18)") (class "Default")
      (node (ref "U5") (pin "18") (pinfunction "DIAG_18") (pintype "unspecified+no_connect"))
    )
    (net (code "83") (name "unconnected-(U5-INDEX-Pad17)") (class "Default")
      (node (ref "U5") (pin "17") (pinfunction "INDEX_17") (pintype "unspecified+no_connect"))
    )
    (net (code "84") (name "unconnected-(U5-PDN-Pad11)") (class "Default")
      (node (ref "U5") (pin "11") (pinfunction "PDN_11") (pintype "unspecified+no_connect"))
    )
    (net (code "85") (name "unconnected-(U5-SPRD-Pad13)") (class "Default")
      (node (ref "U5") (pin "13") (pinfunction "SPRD_13") (pintype "unspecified+no_connect"))
    )
    (net (code "86") (name "unconnected-(U5-UART-Pad12)") (class "Default")
      (node (ref "U5") (pin "12") (pinfunction "UART_12") (pintype "unspecified+no_connect"))
    )
    (net (code "87") (name "unconnected-(U6-DIAG-Pad18)") (class "Default")
      (node (ref "U6") (pin "18") (pinfunction "DIAG_18") (pintype "unspecified+no_connect"))
    )
    (net (code "88") (name "unconnected-(U6-INDEX-Pad17)") (class "Default")
      (node (ref "U6") (pin "17") (pinfunction "INDEX_17") (pintype "unspecified+no_connect"))
    )
    (net (code "89") (name "unconnected-(U6-PDN-Pad11)") (class "Default")
      (node (ref "U6") (pin "11") (pinfunction "PDN_11") (pintype "unspecified+no_connect"))
    )
    (net (code "90") (name "unconnected-(U6-SPRD-Pad13)") (class "Default")
      (node (ref "U6") (pin "13") (pinfunction "SPRD_13") (pintype "unspecified+no_connect"))
    )
    (net (code "91") (name "unconnected-(U6-UART-Pad12)") (class "Default")
      (node (ref "U6") (pin "12") (pinfunction "UART_12") (pintype "unspecified+no_connect"))
    )
    (net (code "92") (name "unconnected-(U8-3V3-Pad1)") (class "Default")
      (node (ref "U8") (pin "1") (pinfunction "3V3_1") (pintype "unspecified+no_connect"))
    )
    (net (code "93") (name "unconnected-(U8-GPIO0-Pad3)") (class "Default")
      (node (ref "U8") (pin "3") (pinfunction "GPIO0_3") (pintype "unspecified+no_connect"))
    )
    (net (code "94") (name "unconnected-(U8-GPIO26-Pad17)") (class "Default")
      (node (ref "U8") (pin "17") (pinfunction "GPIO26_17") (pintype "unspecified+no_connect"))
    )
    (net (code "95") (name "unconnected-(U8-RST-Pad2)") (class "Default")
      (node (ref "U8") (pin "2") (pinfunction "RST_2") (pintype "unspecified+no_connect"))
    )
  )
)
